# mini_controller_m328_2.net
KiCad netlist of a schematic drawn in EAGLE
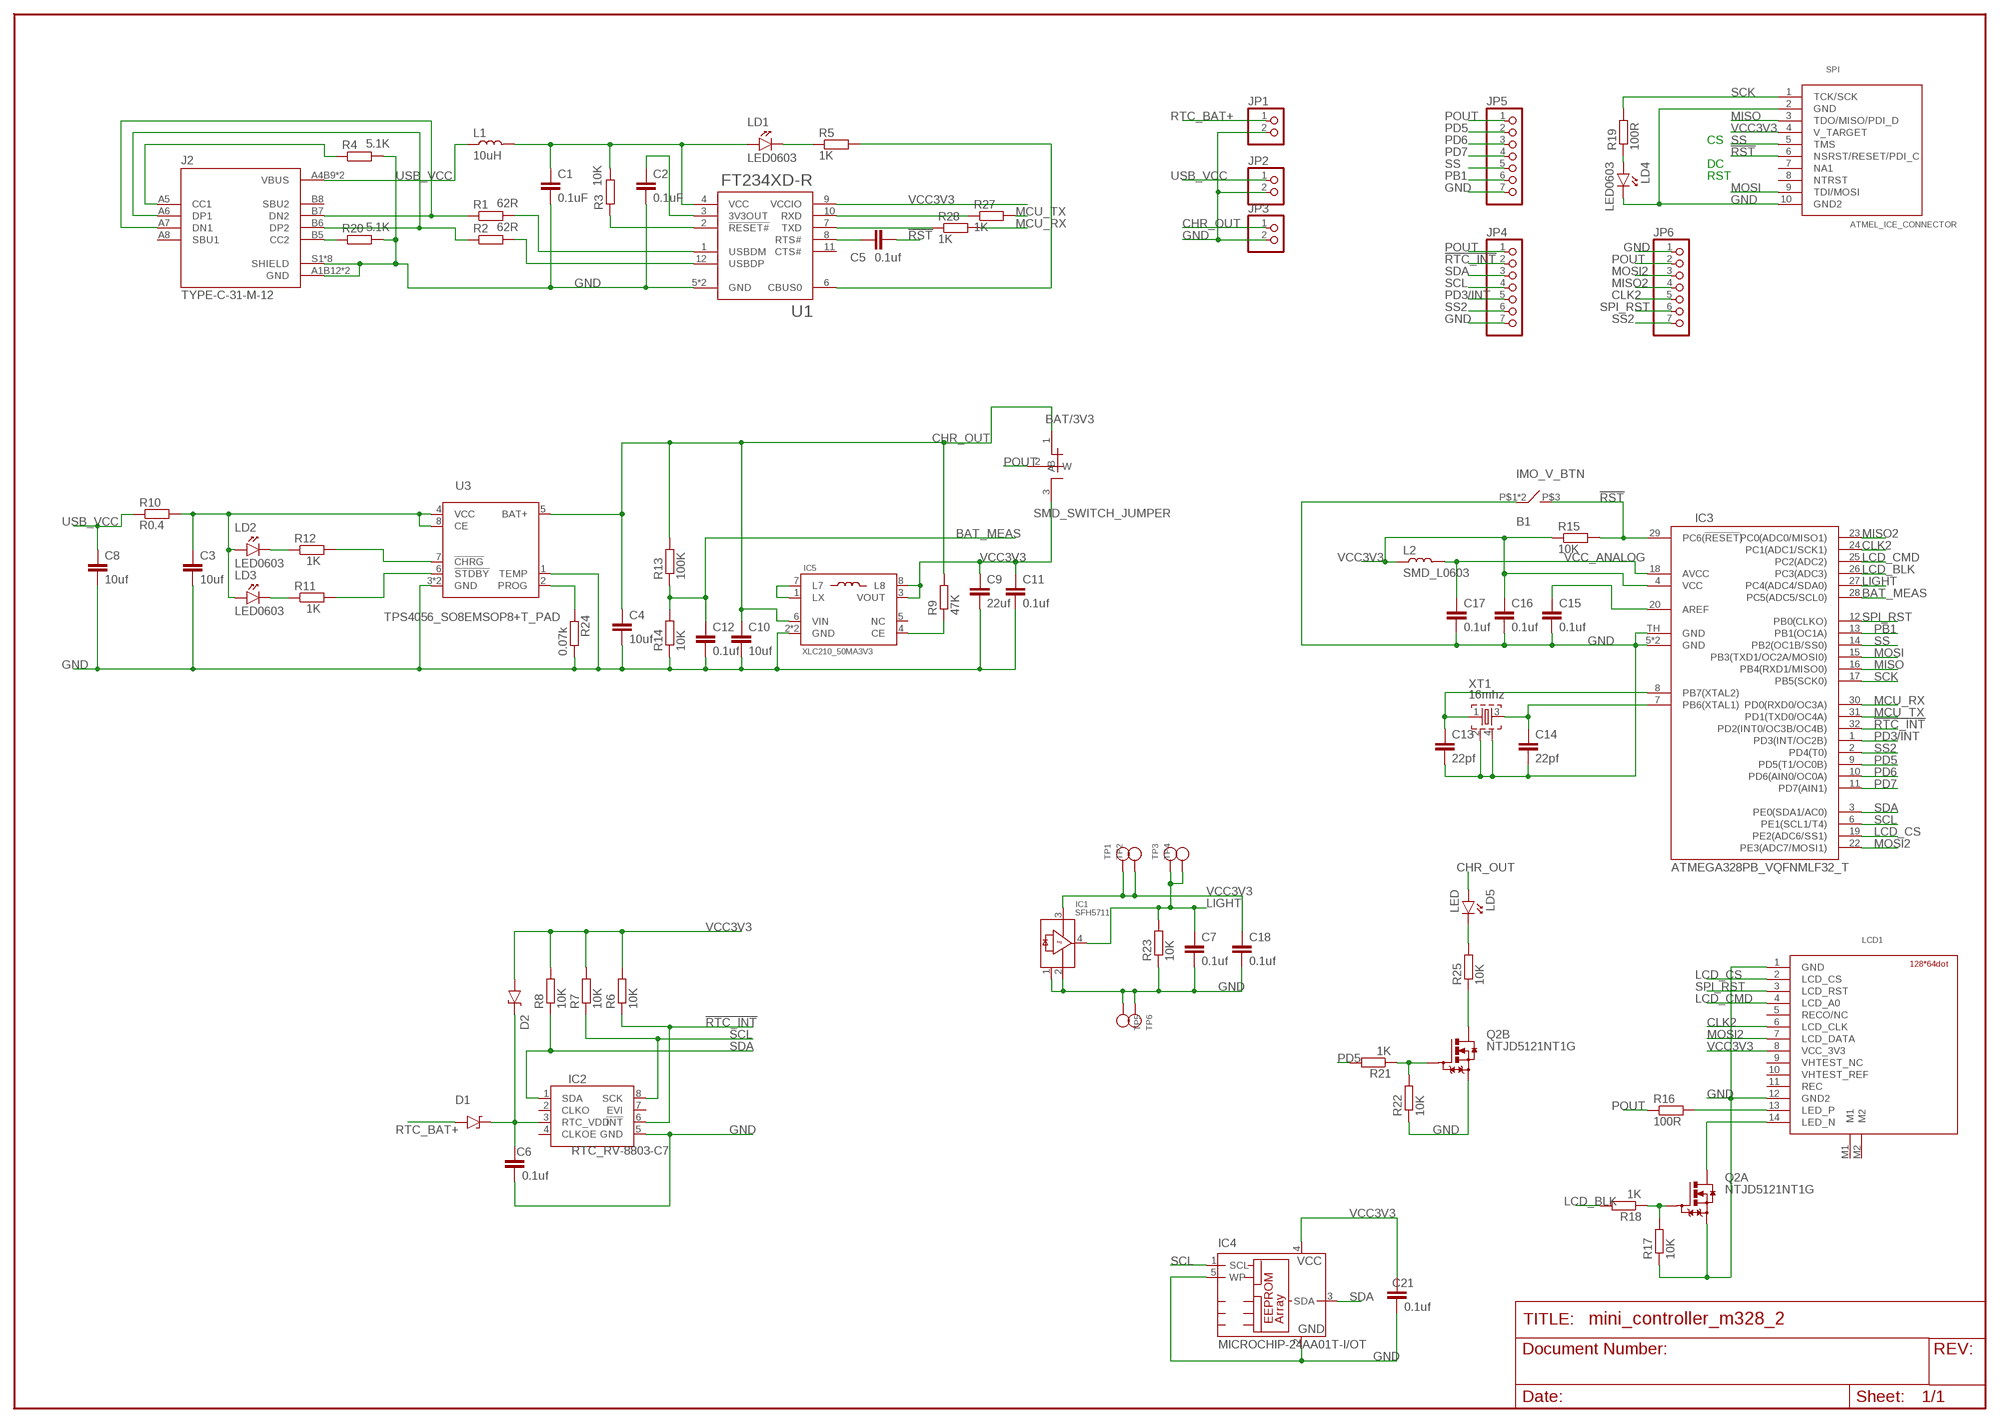
[diagram p0: schematic, sheet 1]

(export (version "E")
  (design (tool "Eeschema 10.0.6"))
  (components
    (comp (ref "B1")
      (value "IMO_V_BTN")
      (footprint "eagle-import:IMO_V_BNN")
      (libsource (lib "eagle-import") (part "IMO_V_BTN"))
    )
    (comp (ref "BAT/3V3")
      (value "SMD_SWITCH_JUMPER")
      (footprint "eagle-import:0603_JUMP")
      (libsource (lib "eagle-import") (part "SMD_SWITCH_JUMPER"))
    )
    (comp (ref "C1")
      (value "0.1uF")
      (footprint "eagle-import:0603")
      (libsource (lib "eagle-import") (part "SMD_C0603"))
    )
    (comp (ref "C2")
      (value "0.1uF")
      (footprint "eagle-import:0603")
      (libsource (lib "eagle-import") (part "SMD_C0603"))
    )
    (comp (ref "C3")
      (value "10uf")
      (footprint "eagle-import:1206")
      (libsource (lib "eagle-import") (part "SMD_C1206"))
    )
    (comp (ref "C4")
      (value "10uf")
      (footprint "eagle-import:1206")
      (libsource (lib "eagle-import") (part "SMD_C1206"))
    )
    (comp (ref "C5")
      (value "0.1uf")
      (footprint "eagle-import:0603")
      (libsource (lib "eagle-import") (part "SMD_C0603"))
    )
    (comp (ref "C6")
      (value "0.1uf")
      (footprint "eagle-import:0603")
      (libsource (lib "eagle-import") (part "SMD_C0603"))
    )
    (comp (ref "C7")
      (value "0.1uf")
      (footprint "eagle-import:0603")
      (libsource (lib "eagle-import") (part "SMD_C0603"))
    )
    (comp (ref "C8")
      (value "10uf")
      (footprint "eagle-import:1206")
      (libsource (lib "eagle-import") (part "SMD_C1206"))
    )
    (comp (ref "C9")
      (value "22uf")
      (footprint "eagle-import:0805")
      (libsource (lib "eagle-import") (part "SMD_C0805"))
    )
    (comp (ref "C10")
      (value "10uf")
      (footprint "eagle-import:0603")
      (libsource (lib "eagle-import") (part "SMD_C0603"))
    )
    (comp (ref "C11")
      (value "0.1uf")
      (footprint "eagle-import:0603")
      (libsource (lib "eagle-import") (part "SMD_C0603"))
    )
    (comp (ref "C12")
      (value "0.1uf")
      (footprint "eagle-import:0603")
      (libsource (lib "eagle-import") (part "SMD_C0603"))
    )
    (comp (ref "C13")
      (value "22pf")
      (footprint "eagle-import:0603")
      (libsource (lib "eagle-import") (part "SMD_C0603"))
    )
    (comp (ref "C14")
      (value "22pf")
      (footprint "eagle-import:0603")
      (libsource (lib "eagle-import") (part "SMD_C0603"))
    )
    (comp (ref "C15")
      (value "0.1uf")
      (footprint "eagle-import:0603")
      (libsource (lib "eagle-import") (part "SMD_C0603"))
    )
    (comp (ref "C16")
      (value "0.1uf")
      (footprint "eagle-import:0603")
      (libsource (lib "eagle-import") (part "SMD_C0603"))
    )
    (comp (ref "C17")
      (value "0.1uf")
      (footprint "eagle-import:0603")
      (libsource (lib "eagle-import") (part "SMD_C0603"))
    )
    (comp (ref "C18")
      (value "0.1uf")
      (footprint "eagle-import:0603")
      (libsource (lib "eagle-import") (part "SMD_C0603"))
    )
    (comp (ref "C21")
      (value "0.1uf")
      (footprint "eagle-import:0603")
      (libsource (lib "eagle-import") (part "SMD_C0603"))
    )
    (comp (ref "D1")
      (value "D_SOD323")
      (footprint "eagle-import:SOD-323_D")
      (libsource (lib "eagle-import") (part "D_SOD323"))
    )
    (comp (ref "D2")
      (value "D_SOD323")
      (footprint "eagle-import:SOD-323_D")
      (libsource (lib "eagle-import") (part "D_SOD323"))
    )
    (comp (ref "IC1")
      (value "SFH5711")
      (footprint "eagle-import:SFH5711")
      (fields (field (name "MF") "OSRAM Opto"))
      (libsource (lib "eagle-import") (part "SFH5711"))
    )
    (comp (ref "IC2")
      (value "RTC_RV-8803-C7")
      (footprint "eagle-import:C7_RTC")
      (libsource (lib "eagle-import") (part "RTC_RV-8803-C7"))
    )
    (comp (ref "IC3")
      (value "ATMEGA328PB_VQFNMLF32_T")
      (footprint "eagle-import:MLF32-TH")
      (libsource (lib "eagle-import") (part "ATMEGA328PB_VQFNMLF32_T"))
    )
    (comp (ref "IC4")
      (value "MICROCHIP-24AA01T-I/OT")
      (footprint "eagle-import:SOT-23(5)")
      (libsource (lib "eagle-import") (part "MICROCHIP-24AA01T-I/OT"))
    )
    (comp (ref "IC5")
      (value "XLC210_50MA3V3")
      (footprint "eagle-import:XCL210_50MA3V3")
      (libsource (lib "eagle-import") (part "XLC210_50MA3V3"))
    )
    (comp (ref "J2")
      (value "TYPE-C-31-M-12")
      (footprint "eagle-import:HRO_TYPE-C-31-M-12")
      (fields (field (name "MF") "HRO Electronics Co., Ltd."))
      (libsource (lib "eagle-import") (part "TYPE-C-31-M-12"))
    )
    (comp (ref "JP1")
      (value "PINHD-1X2")
      (footprint "eagle-import:1X02")
      (libsource (lib "eagle-import") (part "PINHD-1X2"))
    )
    (comp (ref "JP2")
      (value "PINHD-1X2")
      (footprint "eagle-import:1X02")
      (libsource (lib "eagle-import") (part "PINHD-1X2"))
    )
    (comp (ref "JP3")
      (value "PINHD-1X2")
      (footprint "eagle-import:1X02")
      (libsource (lib "eagle-import") (part "PINHD-1X2"))
    )
    (comp (ref "JP4")
      (value "PINHD-1X7")
      (footprint "eagle-import:1X07")
      (libsource (lib "eagle-import") (part "PINHD-1X7"))
    )
    (comp (ref "JP5")
      (value "PINHD-1X7")
      (footprint "eagle-import:1X07")
      (libsource (lib "eagle-import") (part "PINHD-1X7"))
    )
    (comp (ref "JP6")
      (value "PINHD-1X7")
      (footprint "eagle-import:1X07")
      (libsource (lib "eagle-import") (part "PINHD-1X7"))
    )
    (comp (ref "L1")
      (value "10uH")
      (footprint "eagle-import:0603")
      (libsource (lib "eagle-import") (part "SMD_L0603"))
    )
    (comp (ref "L2")
      (value "SMD_L0603")
      (footprint "eagle-import:0603")
      (libsource (lib "eagle-import") (part "SMD_L0603"))
    )
    (comp (ref "LCD1")
      (value "ALE_LCD_128X64")
      (footprint "eagle-import:ALE_LCD_14PIN_CONNECTOR")
      (libsource (lib "eagle-import") (part "ALE_LCD_128X64"))
    )
    (comp (ref "LD1")
      (value "LED0603")
      (footprint "eagle-import:0603_P")
      (libsource (lib "eagle-import") (part "LED0603"))
    )
    (comp (ref "LD2")
      (value "LED0603")
      (footprint "eagle-import:0603_P")
      (libsource (lib "eagle-import") (part "LED0603"))
    )
    (comp (ref "LD3")
      (value "LED0603")
      (footprint "eagle-import:0603_P")
      (libsource (lib "eagle-import") (part "LED0603"))
    )
    (comp (ref "LD4")
      (value "LED0603")
      (footprint "eagle-import:0603_P")
      (libsource (lib "eagle-import") (part "LED0603"))
    )
    (comp (ref "LD5")
      (value "LED")
      (footprint "eagle-import:3MM_DIP_LED")
      (libsource (lib "eagle-import") (part "LED"))
    )
    (comp (ref "Q2")
      (value "NTJD5121NT1G")
      (footprint "eagle-import:SOT363")
      (fields (field (name "MF") "ON SEMICONDUCTOR"))
      (libsource (lib "eagle-import") (part "NTJD5121NT1G"))
    )
    (comp (ref "R1")
      (value "62R")
      (footprint "eagle-import:0603")
      (libsource (lib "eagle-import") (part "SMD_R0603"))
    )
    (comp (ref "R2")
      (value "62R")
      (footprint "eagle-import:0603")
      (libsource (lib "eagle-import") (part "SMD_R0603"))
    )
    (comp (ref "R3")
      (value "10K")
      (footprint "eagle-import:0603")
      (libsource (lib "eagle-import") (part "SMD_R0603"))
    )
    (comp (ref "R4")
      (value "5.1K")
      (footprint "eagle-import:0603")
      (libsource (lib "eagle-import") (part "SMD_R0603"))
    )
    (comp (ref "R5")
      (value "1K")
      (footprint "eagle-import:0603")
      (libsource (lib "eagle-import") (part "SMD_R0603"))
    )
    (comp (ref "R6")
      (value "10K")
      (footprint "eagle-import:0603")
      (libsource (lib "eagle-import") (part "SMD_R0603"))
    )
    (comp (ref "R7")
      (value "10K")
      (footprint "eagle-import:0603")
      (libsource (lib "eagle-import") (part "SMD_R0603"))
    )
    (comp (ref "R8")
      (value "10K")
      (footprint "eagle-import:0603")
      (libsource (lib "eagle-import") (part "SMD_R0603"))
    )
    (comp (ref "R9")
      (value "47K")
      (footprint "eagle-import:0603")
      (libsource (lib "eagle-import") (part "SMD_R0603"))
    )
    (comp (ref "R10")
      (value "R0.4")
      (footprint "eagle-import:1206")
      (libsource (lib "eagle-import") (part "SMD_R1206"))
    )
    (comp (ref "R11")
      (value "1K")
      (footprint "eagle-import:0603")
      (libsource (lib "eagle-import") (part "SMD_R0603"))
    )
    (comp (ref "R12")
      (value "1K")
      (footprint "eagle-import:0603")
      (libsource (lib "eagle-import") (part "SMD_R0603"))
    )
    (comp (ref "R13")
      (value "100K")
      (footprint "eagle-import:0603")
      (libsource (lib "eagle-import") (part "SMD_R0603"))
    )
    (comp (ref "R14")
      (value "10K")
      (footprint "eagle-import:0603")
      (libsource (lib "eagle-import") (part "SMD_R0603"))
    )
    (comp (ref "R15")
      (value "10K")
      (footprint "eagle-import:0603")
      (libsource (lib "eagle-import") (part "SMD_R0603"))
    )
    (comp (ref "R16")
      (value "100R")
      (footprint "eagle-import:0603")
      (libsource (lib "eagle-import") (part "SMD_R0603"))
    )
    (comp (ref "R17")
      (value "10K")
      (footprint "eagle-import:0603")
      (libsource (lib "eagle-import") (part "SMD_R0603"))
    )
    (comp (ref "R18")
      (value "1K")
      (footprint "eagle-import:0603")
      (libsource (lib "eagle-import") (part "SMD_R0603"))
    )
    (comp (ref "R19")
      (value "100R")
      (footprint "eagle-import:0603")
      (libsource (lib "eagle-import") (part "SMD_R0603"))
    )
    (comp (ref "R20")
      (value "5.1K")
      (footprint "eagle-import:0603")
      (libsource (lib "eagle-import") (part "SMD_R0603"))
    )
    (comp (ref "R21")
      (value "1K")
      (footprint "eagle-import:0603")
      (libsource (lib "eagle-import") (part "SMD_R0603"))
    )
    (comp (ref "R22")
      (value "10K")
      (footprint "eagle-import:0603")
      (libsource (lib "eagle-import") (part "SMD_R0603"))
    )
    (comp (ref "R23")
      (value "10K")
      (footprint "eagle-import:0603")
      (libsource (lib "eagle-import") (part "SMD_R0603"))
    )
    (comp (ref "R24")
      (value "0.07k")
      (footprint "eagle-import:0603")
      (libsource (lib "eagle-import") (part "SMD_R0603"))
    )
    (comp (ref "R25")
      (value "10K")
      (footprint "eagle-import:0603")
      (libsource (lib "eagle-import") (part "SMD_R0603"))
    )
    (comp (ref "R27")
      (value "1K")
      (footprint "eagle-import:0603")
      (libsource (lib "eagle-import") (part "SMD_R0603"))
    )
    (comp (ref "R28")
      (value "1K")
      (footprint "eagle-import:0603")
      (libsource (lib "eagle-import") (part "SMD_R0603"))
    )
    (comp (ref "SPI")
      (value "ATMEL_ICE_CONNECTOR")
      (footprint "eagle-import:MINI10P_SPI_JTAG_PDI")
      (libsource (lib "eagle-import") (part "ATMEL_ICE_CONNECTOR"))
    )
    (comp (ref "TP1")
      (value "TEST_POINT_D2MM")
      (footprint "eagle-import:TP")
      (libsource (lib "eagle-import") (part "TEST_POINT_D2MM"))
    )
    (comp (ref "TP2")
      (value "TEST_POINT_D2MM")
      (footprint "eagle-import:TP")
      (libsource (lib "eagle-import") (part "TEST_POINT_D2MM"))
    )
    (comp (ref "TP3")
      (value "TEST_POINT_D2MM")
      (footprint "eagle-import:TP")
      (libsource (lib "eagle-import") (part "TEST_POINT_D2MM"))
    )
    (comp (ref "TP4")
      (value "TEST_POINT_D2MM")
      (footprint "eagle-import:TP")
      (libsource (lib "eagle-import") (part "TEST_POINT_D2MM"))
    )
    (comp (ref "TP5")
      (value "TEST_POINT_D2MM")
      (footprint "eagle-import:TP")
      (libsource (lib "eagle-import") (part "TEST_POINT_D2MM"))
    )
    (comp (ref "TP6")
      (value "TEST_POINT_D2MM")
      (footprint "eagle-import:TP")
      (libsource (lib "eagle-import") (part "TEST_POINT_D2MM"))
    )
    (comp (ref "U1")
      (value "FT234XD-R")
      (footprint "eagle-import:IC_FT234XD-R")
      (fields (field (name "MF") "FTDI,"))
      (libsource (lib "eagle-import") (part "FT234XD-R"))
    )
    (comp (ref "U3")
      (value "TPS4056_SO8EMSOP8+T_PAD")
      (footprint "eagle-import:EMSOP8+TPAD")
      (libsource (lib "eagle-import") (part "TPS4056_SO8EMSOP8+T_PAD"))
    )
    (comp (ref "XT1")
      (value "16mhz")
      (footprint "eagle-import:QUARTZ_3X3MM")
      (libsource (lib "eagle-import") (part "QUARTZ_ZQ"))
    )
  )
  (nets
    (net (code "1") (name "/BAT_MEAS") (class "Default")
      (node (ref "C12") (pin "1") (pinfunction "1_1") (pintype "passive"))
      (node (ref "IC3") (pin "28") (pinfunction "PC5(ADC5/SCL0)_28") (pintype "bidirectional"))
      (node (ref "R13") (pin "1") (pinfunction "1_1") (pintype "passive"))
      (node (ref "R14") (pin "2") (pinfunction "2_2") (pintype "passive"))
    )
    (net (code "2") (name "/CHR_OUT") (class "Default")
      (node (ref "BAT/3V3") (pin "1") (pinfunction "A_1") (pintype "bidirectional"))
      (node (ref "C10") (pin "1") (pinfunction "1_1") (pintype "passive"))
      (node (ref "C4") (pin "1") (pinfunction "1_1") (pintype "passive"))
      (node (ref "IC5") (pin "6") (pinfunction "VIN_6") (pintype "bidirectional"))
      (node (ref "JP3") (pin "1") (pinfunction "1_1") (pintype "passive"))
      (node (ref "LD5") (pin "A") (pinfunction "A_A") (pintype "bidirectional"))
      (node (ref "R13") (pin "2") (pinfunction "2_2") (pintype "passive"))
      (node (ref "R9") (pin "2") (pinfunction "2_2") (pintype "passive"))
      (node (ref "U3") (pin "5") (pinfunction "BAT+_5") (pintype "bidirectional"))
    )
    (net (code "3") (name "/CLK2") (class "Default")
      (node (ref "IC3") (pin "24") (pinfunction "PC1(ADC1/SCK1)_24") (pintype "bidirectional"))
      (node (ref "JP6") (pin "5") (pinfunction "5_5") (pintype "passive"))
      (node (ref "LCD1") (pin "6") (pinfunction "LCD_CLK_6") (pintype "bidirectional"))
    )
    (net (code "4") (name "/GND") (class "Default")
      (node (ref "B1") (pin "P$1") (pinfunction "1_P$1") (pintype "bidirectional"))
      (node (ref "B1") (pin "P$2") (pinfunction "1_P$2") (pintype "bidirectional"))
      (node (ref "C1") (pin "2") (pinfunction "2_2") (pintype "passive"))
      (node (ref "C10") (pin "2") (pinfunction "2_2") (pintype "passive"))
      (node (ref "C11") (pin "2") (pinfunction "2_2") (pintype "passive"))
      (node (ref "C12") (pin "2") (pinfunction "2_2") (pintype "passive"))
      (node (ref "C13") (pin "2") (pinfunction "2_2") (pintype "passive"))
      (node (ref "C14") (pin "2") (pinfunction "2_2") (pintype "passive"))
      (node (ref "C15") (pin "2") (pinfunction "2_2") (pintype "passive"))
      (node (ref "C16") (pin "2") (pinfunction "2_2") (pintype "passive"))
      (node (ref "C17") (pin "2") (pinfunction "2_2") (pintype "passive"))
      (node (ref "C18") (pin "2") (pinfunction "2_2") (pintype "passive"))
      (node (ref "C2") (pin "2") (pinfunction "2_2") (pintype "passive"))
      (node (ref "C21") (pin "2") (pinfunction "2_2") (pintype "passive"))
      (node (ref "C3") (pin "2") (pinfunction "2_2") (pintype "passive"))
      (node (ref "C4") (pin "2") (pinfunction "2_2") (pintype "passive"))
      (node (ref "C6") (pin "2") (pinfunction "2_2") (pintype "passive"))
      (node (ref "C7") (pin "2") (pinfunction "2_2") (pintype "passive"))
      (node (ref "C8") (pin "2") (pinfunction "2_2") (pintype "passive"))
      (node (ref "C9") (pin "2") (pinfunction "2_2") (pintype "passive"))
      (node (ref "IC1") (pin "1") (pinfunction "1_1") (pintype "bidirectional"))
      (node (ref "IC1") (pin "2") (pinfunction "2_2") (pintype "bidirectional"))
      (node (ref "IC2") (pin "5") (pinfunction "GND_5") (pintype "bidirectional"))
      (node (ref "IC3") (pin "21") (pinfunction "GND_21") (pintype "power_in"))
      (node (ref "IC3") (pin "5") (pinfunction "GND_5") (pintype "power_in"))
      (node (ref "IC3") (pin "TH") (pinfunction "GND_TH") (pintype "power_in"))
      (node (ref "IC4") (pin "2") (pinfunction "GND_2") (pintype "power_in"))
      (node (ref "IC4") (pin "5") (pinfunction "WP_5") (pintype "input"))
      (node (ref "IC5") (pin "2") (pinfunction "GND_2") (pintype "bidirectional"))
      (node (ref "IC5") (pin "9") (pinfunction "GND_9") (pintype "bidirectional"))
      (node (ref "J2") (pin "A1B12") (pinfunction "GND_A1B12") (pintype "power_in"))
      (node (ref "J2") (pin "B1A12") (pinfunction "GND_B1A12") (pintype "power_in"))
      (node (ref "J2") (pin "S1") (pinfunction "SHIELD_S1") (pintype "passive"))
      (node (ref "J2") (pin "S2") (pinfunction "SHIELD_S2") (pintype "passive"))
      (node (ref "J2") (pin "S3") (pinfunction "SHIELD_S3") (pintype "passive"))
      (node (ref "J2") (pin "S4") (pinfunction "SHIELD_S4") (pintype "passive"))
      (node (ref "J2") (pin "S5") (pinfunction "SHIELD_S5") (pintype "passive"))
      (node (ref "J2") (pin "S6") (pinfunction "SHIELD_S6") (pintype "passive"))
      (node (ref "J2") (pin "S7") (pinfunction "SHIELD_S7") (pintype "passive"))
      (node (ref "J2") (pin "S8") (pinfunction "SHIELD_S8") (pintype "passive"))
      (node (ref "JP1") (pin "2") (pinfunction "2_2") (pintype "passive"))
      (node (ref "JP2") (pin "2") (pinfunction "2_2") (pintype "passive"))
      (node (ref "JP3") (pin "2") (pinfunction "2_2") (pintype "passive"))
      (node (ref "JP4") (pin "7") (pinfunction "7_7") (pintype "passive"))
      (node (ref "JP5") (pin "7") (pinfunction "7_7") (pintype "passive"))
      (node (ref "JP6") (pin "1") (pinfunction "1_1") (pintype "passive"))
      (node (ref "LCD1") (pin "1") (pinfunction "GND_1") (pintype "bidirectional"))
      (node (ref "LCD1") (pin "12") (pinfunction "GND2_12") (pintype "bidirectional"))
      (node (ref "LD4") (pin "1") (pinfunction "K_1") (pintype "bidirectional"))
      (node (ref "Q2") (pin "1") (pinfunction "S_1") (pintype "passive"))
      (node (ref "Q2") (pin "4") (pinfunction "S_4") (pintype "passive"))
      (node (ref "R14") (pin "1") (pinfunction "1_1") (pintype "passive"))
      (node (ref "R17") (pin "1") (pinfunction "1_1") (pintype "passive"))
      (node (ref "R20") (pin "2") (pinfunction "2_2") (pintype "passive"))
      (node (ref "R22") (pin "1") (pinfunction "1_1") (pintype "passive"))
      (node (ref "R23") (pin "1") (pinfunction "1_1") (pintype "passive"))
      (node (ref "R24") (pin "2") (pinfunction "2_2") (pintype "passive"))
      (node (ref "R4") (pin "2") (pinfunction "2_2") (pintype "passive"))
      (node (ref "SPI") (pin "10") (pinfunction "GND2_10") (pintype "bidirectional"))
      (node (ref "SPI") (pin "2") (pinfunction "GND_2") (pintype "bidirectional"))
      (node (ref "TP5") (pin "P$1") (pinfunction "1_P$1") (pintype "bidirectional"))
      (node (ref "TP6") (pin "P$1") (pinfunction "1_P$1") (pintype "bidirectional"))
      (node (ref "U1") (pin "13") (pinfunction "GND_13") (pintype "power_in"))
      (node (ref "U1") (pin "5") (pinfunction "GND_5") (pintype "power_in"))
      (node (ref "U3") (pin "1") (pinfunction "TEMP_1") (pintype "bidirectional"))
      (node (ref "U3") (pin "3") (pinfunction "GND_3") (pintype "bidirectional"))
      (node (ref "U3") (pin "TPAD") (pinfunction "GND_TPAD") (pintype "bidirectional"))
      (node (ref "XT1") (pin "2") (pinfunction "2_2") (pintype "passive"))
      (node (ref "XT1") (pin "4") (pinfunction "4_4") (pintype "passive"))
    )
    (net (code "5") (name "/LCD_BLK") (class "Default")
      (node (ref "IC3") (pin "26") (pinfunction "PC3(ADC3)_26") (pintype "bidirectional"))
      (node (ref "R18") (pin "2") (pinfunction "2_2") (pintype "passive"))
    )
    (net (code "6") (name "/LCD_CMD") (class "Default")
      (node (ref "IC3") (pin "25") (pinfunction "PC2(ADC2)_25") (pintype "bidirectional"))
      (node (ref "LCD1") (pin "4") (pinfunction "LCD_A0_4") (pintype "bidirectional"))
    )
    (net (code "7") (name "/LCD_CS") (class "Default")
      (node (ref "IC3") (pin "19") (pinfunction "PE2(ADC6/SS1)_19") (pintype "bidirectional"))
      (node (ref "LCD1") (pin "2") (pinfunction "LCD_CS_2") (pintype "bidirectional"))
    )
    (net (code "8") (name "/LIGHT") (class "Default")
      (node (ref "C7") (pin "1") (pinfunction "1_1") (pintype "passive"))
      (node (ref "IC1") (pin "4") (pinfunction "4_4") (pintype "bidirectional"))
      (node (ref "IC3") (pin "27") (pinfunction "PC4(ADC4/SDA0)_27") (pintype "bidirectional"))
      (node (ref "R23") (pin "2") (pinfunction "2_2") (pintype "passive"))
      (node (ref "TP3") (pin "P$1") (pinfunction "1_P$1") (pintype "bidirectional"))
      (node (ref "TP4") (pin "P$1") (pinfunction "1_P$1") (pintype "bidirectional"))
    )
    (net (code "9") (name "/MCU_RX") (class "Default")
      (node (ref "IC3") (pin "30") (pinfunction "PD0(RXD0/OC3A)_30") (pintype "bidirectional"))
      (node (ref "R28") (pin "2") (pinfunction "2_2") (pintype "passive"))
    )
    (net (code "10") (name "/MCU_TX") (class "Default")
      (node (ref "IC3") (pin "31") (pinfunction "PD1(TXD0/OC4A)_31") (pintype "bidirectional"))
      (node (ref "R27") (pin "2") (pinfunction "2_2") (pintype "passive"))
    )
    (net (code "11") (name "/MISO") (class "Default")
      (node (ref "IC3") (pin "16") (pinfunction "PB4(RXD1/MISO0)_16") (pintype "bidirectional"))
      (node (ref "SPI") (pin "3") (pinfunction "TDO/MISO/PDI_D_3") (pintype "bidirectional"))
    )
    (net (code "12") (name "/MISO2") (class "Default")
      (node (ref "IC3") (pin "23") (pinfunction "PC0(ADC0/MISO1)_23") (pintype "bidirectional"))
      (node (ref "JP6") (pin "4") (pinfunction "4_4") (pintype "passive"))
    )
    (net (code "13") (name "/MOSI") (class "Default")
      (node (ref "IC3") (pin "15") (pinfunction "PB3(TXD1/OC2A/MOSI0)_15") (pintype "bidirectional"))
      (node (ref "SPI") (pin "9") (pinfunction "TDI/MOSI_9") (pintype "bidirectional"))
    )
    (net (code "14") (name "/MOSI2") (class "Default")
      (node (ref "IC3") (pin "22") (pinfunction "PE3(ADC7/MOSI1)_22") (pintype "bidirectional"))
      (node (ref "JP6") (pin "3") (pinfunction "3_3") (pintype "passive"))
      (node (ref "LCD1") (pin "7") (pinfunction "LCD_DATA_7") (pintype "bidirectional"))
    )
    (net (code "15") (name "/PB1") (class "Default")
      (node (ref "IC3") (pin "13") (pinfunction "PB1(OC1A)_13") (pintype "bidirectional"))
      (node (ref "JP5") (pin "6") (pinfunction "6_6") (pintype "passive"))
    )
    (net (code "16") (name "/PD3{slash}INT") (class "Default")
      (node (ref "IC3") (pin "1") (pinfunction "PD3(INT/OC2B)_1") (pintype "bidirectional"))
      (node (ref "JP4") (pin "5") (pinfunction "5_5") (pintype "passive"))
    )
    (net (code "17") (name "/PD5") (class "Default")
      (node (ref "IC3") (pin "9") (pinfunction "PD5(T1/OC0B)_9") (pintype "bidirectional"))
      (node (ref "JP5") (pin "2") (pinfunction "2_2") (pintype "passive"))
      (node (ref "R21") (pin "2") (pinfunction "2_2") (pintype "passive"))
    )
    (net (code "18") (name "/PD6") (class "Default")
      (node (ref "IC3") (pin "10") (pinfunction "PD6(AIN0/OC0A)_10") (pintype "bidirectional"))
      (node (ref "JP5") (pin "3") (pinfunction "3_3") (pintype "passive"))
    )
    (net (code "19") (name "/PD7") (class "Default")
      (node (ref "IC3") (pin "11") (pinfunction "PD7(AIN1)_11") (pintype "bidirectional"))
      (node (ref "JP5") (pin "4") (pinfunction "4_4") (pintype "passive"))
    )
    (net (code "20") (name "/POUT") (class "Default")
      (node (ref "BAT/3V3") (pin "2") (pinfunction "W_2") (pintype "bidirectional"))
      (node (ref "JP4") (pin "1") (pinfunction "1_1") (pintype "passive"))
      (node (ref "JP5") (pin "1") (pinfunction "1_1") (pintype "passive"))
      (node (ref "JP6") (pin "2") (pinfunction "2_2") (pintype "passive"))
      (node (ref "R16") (pin "1") (pinfunction "1_1") (pintype "passive"))
    )
    (net (code "21") (name "/RTC_BAT+") (class "Default")
      (node (ref "D1") (pin "A") (pinfunction "A_A") (pintype "bidirectional"))
      (node (ref "JP1") (pin "1") (pinfunction "1_1") (pintype "passive"))
    )
    (net (code "22") (name "/SCK") (class "Default")
      (node (ref "IC3") (pin "17") (pinfunction "PB5(SCK0)_17") (pintype "bidirectional"))
      (node (ref "R19") (pin "2") (pinfunction "2_2") (pintype "passive"))
      (node (ref "SPI") (pin "1") (pinfunction "TCK/SCK_1") (pintype "bidirectional"))
    )
    (net (code "23") (name "/SCL") (class "Default")
      (node (ref "IC2") (pin "8") (pinfunction "SCK_8") (pintype "bidirectional"))
      (node (ref "IC3") (pin "6") (pinfunction "PE1(SCL1/T4)_6") (pintype "bidirectional"))
      (node (ref "IC4") (pin "1") (pinfunction "SCL_1") (pintype "input"))
      (node (ref "JP4") (pin "4") (pinfunction "4_4") (pintype "passive"))
      (node (ref "R7") (pin "1") (pinfunction "1_1") (pintype "passive"))
    )
    (net (code "24") (name "/SDA") (class "Default")
      (node (ref "IC2") (pin "1") (pinfunction "SDA_1") (pintype "bidirectional"))
      (node (ref "IC3") (pin "3") (pinfunction "PE0(SDA1/AC0)_3") (pintype "bidirectional"))
      (node (ref "IC4") (pin "3") (pinfunction "SDA_3") (pintype "bidirectional"))
      (node (ref "JP4") (pin "3") (pinfunction "3_3") (pintype "passive"))
      (node (ref "R8") (pin "1") (pinfunction "1_1") (pintype "passive"))
    )
    (net (code "25") (name "/SPI_RST") (class "Default")
      (node (ref "IC3") (pin "12") (pinfunction "PB0(CLKO)_12") (pintype "bidirectional"))
      (node (ref "JP6") (pin "6") (pinfunction "6_6") (pintype "passive"))
      (node (ref "LCD1") (pin "3") (pinfunction "LCD_RST_3") (pintype "bidirectional"))
    )
    (net (code "26") (name "/SS") (class "Default")
      (node (ref "IC3") (pin "14") (pinfunction "PB2(OC1B/SS0)_14") (pintype "bidirectional"))
      (node (ref "JP5") (pin "5") (pinfunction "5_5") (pintype "passive"))
      (node (ref "SPI") (pin "5") (pinfunction "TMS_5") (pintype "bidirectional"))
    )
    (net (code "27") (name "/SS2") (class "Default")
      (node (ref "IC3") (pin "2") (pinfunction "PD4(T0)_2") (pintype "bidirectional"))
      (node (ref "JP4") (pin "6") (pinfunction "6_6") (pintype "passive"))
      (node (ref "JP6") (pin "7") (pinfunction "7_7") (pintype "passive"))
    )
    (net (code "28") (name "/USB_VCC") (class "Default")
      (node (ref "C8") (pin "1") (pinfunction "1_1") (pintype "passive"))
      (node (ref "J2") (pin "A4B9") (pinfunction "VBUS_A4B9") (pintype "power_in"))
      (node (ref "J2") (pin "B4A9") (pinfunction "VBUS_B4A9") (pintype "power_in"))
      (node (ref "JP2") (pin "1") (pinfunction "1_1") (pintype "passive"))
      (node (ref "L1") (pin "1") (pinfunction "1_1") (pintype "passive"))
      (node (ref "R10") (pin "1") (pinfunction "1_1") (pintype "passive"))
    )
    (net (code "29") (name "/VCC3V3") (class "Default")
      (node (ref "BAT/3V3") (pin "3") (pinfunction "B_3") (pintype "bidirectional"))
      (node (ref "C11") (pin "1") (pinfunction "1_1") (pintype "passive"))
      (node (ref "C16") (pin "1") (pinfunction "1_1") (pintype "passive"))
      (node (ref "C18") (pin "1") (pinfunction "1_1") (pintype "passive"))
      (node (ref "C21") (pin "1") (pinfunction "1_1") (pintype "passive"))
      (node (ref "C9") (pin "1") (pinfunction "1_1") (pintype "passive"))
      (node (ref "D2") (pin "A") (pinfunction "A_A") (pintype "bidirectional"))
      (node (ref "IC1") (pin "3") (pinfunction "3_3") (pintype "bidirectional"))
      (node (ref "IC3") (pin "4") (pinfunction "VCC_4") (pintype "power_in"))
      (node (ref "IC4") (pin "4") (pinfunction "VCC_4") (pintype "power_in"))
      (node (ref "IC5") (pin "3") (pinfunction "VOUT_3") (pintype "bidirectional"))
      (node (ref "IC5") (pin "8") (pinfunction "L8_8") (pintype "bidirectional"))
      (node (ref "L2") (pin "1") (pinfunction "1_1") (pintype "passive"))
      (node (ref "LCD1") (pin "8") (pinfunction "VCC_3V3_8") (pintype "bidirectional"))
      (node (ref "R15") (pin "1") (pinfunction "1_1") (pintype "passive"))
      (node (ref "R6") (pin "2") (pinfunction "2_2") (pintype "passive"))
      (node (ref "R7") (pin "2") (pinfunction "2_2") (pintype "passive"))
      (node (ref "R8") (pin "2") (pinfunction "2_2") (pintype "passive"))
      (node (ref "SPI") (pin "4") (pinfunction "V_TARGET_4") (pintype "bidirectional"))
      (node (ref "TP1") (pin "P$1") (pinfunction "1_P$1") (pintype "bidirectional"))
      (node (ref "TP2") (pin "P$1") (pinfunction "1_P$1") (pintype "bidirectional"))
      (node (ref "U1") (pin "9") (pinfunction "VCCIO_9") (pintype "power_in"))
    )
    (net (code "30") (name "/VCC_ANALOG") (class "Default")
      (node (ref "C17") (pin "1") (pinfunction "1_1") (pintype "passive"))
      (node (ref "IC3") (pin "18") (pinfunction "AVCC_18") (pintype "power_in"))
      (node (ref "L2") (pin "2") (pinfunction "2_2") (pintype "passive"))
    )
    (net (code "31") (name "/~{RST}") (class "Default")
      (node (ref "B1") (pin "P$3") (pinfunction "4_P$3") (pintype "bidirectional"))
      (node (ref "C5") (pin "2") (pinfunction "2_2") (pintype "passive"))
      (node (ref "IC3") (pin "29") (pinfunction "PC6(~{RESET})_29") (pintype "bidirectional"))
      (node (ref "R15") (pin "2") (pinfunction "2_2") (pintype "passive"))
      (node (ref "SPI") (pin "6") (pinfunction "NSRST/RESET/PDI_C_6") (pintype "bidirectional"))
    )
    (net (code "32") (name "/~{RTC_INT}") (class "Default")
      (node (ref "IC2") (pin "6") (pinfunction "~{INT}_6") (pintype "bidirectional"))
      (node (ref "IC3") (pin "32") (pinfunction "PD2(INT0/OC3B/OC4B)_32") (pintype "bidirectional"))
      (node (ref "JP4") (pin "2") (pinfunction "2_2") (pintype "passive"))
      (node (ref "R6") (pin "1") (pinfunction "1_1") (pintype "passive"))
    )
    (net (code "33") (name "Net-(IC2-RTC_VDD)") (class "Default")
      (node (ref "C6") (pin "1") (pinfunction "1_1") (pintype "passive"))
      (node (ref "D1") (pin "K") (pinfunction "K_K") (pintype "bidirectional"))
      (node (ref "D2") (pin "K") (pinfunction "K_K") (pintype "bidirectional"))
      (node (ref "IC2") (pin "3") (pinfunction "RTC_VDD_3") (pintype "bidirectional"))
    )
    (net (code "34") (name "Net-(IC3-AREF)") (class "Default")
      (node (ref "C15") (pin "1") (pinfunction "1_1") (pintype "passive"))
      (node (ref "IC3") (pin "20") (pinfunction "AREF_20") (pintype "passive"))
    )
    (net (code "35") (name "Net-(IC3-PB6(XTAL1))") (class "Default")
      (node (ref "C14") (pin "1") (pinfunction "1_1") (pintype "passive"))
      (node (ref "IC3") (pin "7") (pinfunction "PB6(XTAL1)_7") (pintype "bidirectional"))
      (node (ref "XT1") (pin "3") (pinfunction "3_3") (pintype "passive"))
    )
    (net (code "36") (name "Net-(IC3-PB7(XTAL2))") (class "Default")
      (node (ref "C13") (pin "1") (pinfunction "1_1") (pintype "passive"))
      (node (ref "IC3") (pin "8") (pinfunction "PB7(XTAL2)_8") (pintype "bidirectional"))
      (node (ref "XT1") (pin "1") (pinfunction "1_1") (pintype "passive"))
    )
    (net (code "37") (name "Net-(IC5-CE)") (class "Default")
      (node (ref "IC5") (pin "4") (pinfunction "CE_4") (pintype "bidirectional"))
      (node (ref "R9") (pin "1") (pinfunction "1_1") (pintype "passive"))
    )
    (net (code "38") (name "Net-(IC5-L7)") (class "Default")
      (node (ref "IC5") (pin "1") (pinfunction "LX_1") (pintype "bidirectional"))
      (node (ref "IC5") (pin "7") (pinfunction "L7_7") (pintype "bidirectional"))
    )
    (net (code "39") (name "Net-(J2-CC1)") (class "Default")
      (node (ref "J2") (pin "A5") (pinfunction "CC1_A5") (pintype "bidirectional"))
      (node (ref "R4") (pin "1") (pinfunction "1_1") (pintype "passive"))
    )
    (net (code "40") (name "Net-(J2-CC2)") (class "Default")
      (node (ref "J2") (pin "B5") (pinfunction "CC2_B5") (pintype "bidirectional"))
      (node (ref "R20") (pin "1") (pinfunction "1_1") (pintype "passive"))
    )
    (net (code "41") (name "Net-(J2-DN1)") (class "Default")
      (node (ref "J2") (pin "A7") (pinfunction "DN1_A7") (pintype "bidirectional"))
      (node (ref "J2") (pin "B7") (pinfunction "DN2_B7") (pintype "bidirectional"))
      (node (ref "R1") (pin "1") (pinfunction "1_1") (pintype "passive"))
    )
    (net (code "42") (name "Net-(J2-DP1)") (class "Default")
      (node (ref "J2") (pin "A6") (pinfunction "DP1_A6") (pintype "bidirectional"))
      (node (ref "J2") (pin "B6") (pinfunction "DP2_B6") (pintype "bidirectional"))
      (node (ref "R2") (pin "1") (pinfunction "1_1") (pintype "passive"))
    )
    (net (code "43") (name "Net-(LCD1-LED_N)") (class "Default")
      (node (ref "LCD1") (pin "14") (pinfunction "LED_N_14") (pintype "bidirectional"))
      (node (ref "Q2") (pin "6") (pinfunction "D_6") (pintype "passive"))
    )
    (net (code "44") (name "Net-(LCD1-LED_P)") (class "Default")
      (node (ref "LCD1") (pin "13") (pinfunction "LED_P_13") (pintype "bidirectional"))
      (node (ref "R16") (pin "2") (pinfunction "2_2") (pintype "passive"))
    )
    (net (code "45") (name "Net-(LD1-A)") (class "Default")
      (node (ref "C1") (pin "1") (pinfunction "1_1") (pintype "passive"))
      (node (ref "L1") (pin "2") (pinfunction "2_2") (pintype "passive"))
      (node (ref "LD1") (pin "2") (pinfunction "A_2") (pintype "bidirectional"))
      (node (ref "R3") (pin "2") (pinfunction "2_2") (pintype "passive"))
      (node (ref "U1") (pin "4") (pinfunction "VCC_4") (pintype "power_in"))
    )
    (net (code "46") (name "Net-(LD1-K)") (class "Default")
      (node (ref "LD1") (pin "1") (pinfunction "K_1") (pintype "bidirectional"))
      (node (ref "R5") (pin "1") (pinfunction "1_1") (pintype "passive"))
    )
    (net (code "47") (name "Net-(LD2-A)") (class "Default")
      (node (ref "C3") (pin "1") (pinfunction "1_1") (pintype "passive"))
      (node (ref "LD2") (pin "2") (pinfunction "A_2") (pintype "bidirectional"))
      (node (ref "LD3") (pin "2") (pinfunction "A_2") (pintype "bidirectional"))
      (node (ref "R10") (pin "2") (pinfunction "2_2") (pintype "passive"))
      (node (ref "U3") (pin "4") (pinfunction "VCC_4") (pintype "bidirectional"))
      (node (ref "U3") (pin "8") (pinfunction "CE_8") (pintype "bidirectional"))
    )
    (net (code "48") (name "Net-(LD2-K)") (class "Default")
      (node (ref "LD2") (pin "1") (pinfunction "K_1") (pintype "bidirectional"))
      (node (ref "R12") (pin "1") (pinfunction "1_1") (pintype "passive"))
    )
    (net (code "49") (name "Net-(LD3-K)") (class "Default")
      (node (ref "LD3") (pin "1") (pinfunction "K_1") (pintype "bidirectional"))
      (node (ref "R11") (pin "1") (pinfunction "1_1") (pintype "passive"))
    )
    (net (code "50") (name "Net-(LD4-A)") (class "Default")
      (node (ref "LD4") (pin "2") (pinfunction "A_2") (pintype "bidirectional"))
      (node (ref "R19") (pin "1") (pinfunction "1_1") (pintype "passive"))
    )
    (net (code "51") (name "Net-(LD5-PadK)") (class "Default")
      (node (ref "LD5") (pin "K") (pinfunction "K_K") (pintype "bidirectional"))
      (node (ref "R25") (pin "2") (pinfunction "2_2") (pintype "passive"))
    )
    (net (code "52") (name "Net-(Q2A-G)") (class "Default")
      (node (ref "Q2") (pin "2") (pinfunction "G_2") (pintype "passive"))
      (node (ref "R17") (pin "2") (pinfunction "2_2") (pintype "passive"))
      (node (ref "R18") (pin "1") (pinfunction "1_1") (pintype "passive"))
    )
    (net (code "53") (name "Net-(Q2B-D)") (class "Default")
      (node (ref "Q2") (pin "3") (pinfunction "D_3") (pintype "passive"))
      (node (ref "R25") (pin "1") (pinfunction "1_1") (pintype "passive"))
    )
    (net (code "54") (name "Net-(Q2B-G)") (class "Default")
      (node (ref "Q2") (pin "5") (pinfunction "G_5") (pintype "passive"))
      (node (ref "R21") (pin "1") (pinfunction "1_1") (pintype "passive"))
      (node (ref "R22") (pin "2") (pinfunction "2_2") (pintype "passive"))
    )
    (net (code "55") (name "Net-(U1-3V3OUT)") (class "Default")
      (node (ref "C2") (pin "1") (pinfunction "1_1") (pintype "passive"))
      (node (ref "U1") (pin "3") (pinfunction "3V3OUT_3") (pintype "output"))
    )
    (net (code "56") (name "Net-(U1-CBUS0)") (class "Default")
      (node (ref "R5") (pin "2") (pinfunction "2_2") (pintype "passive"))
      (node (ref "U1") (pin "6") (pinfunction "CBUS0_6") (pintype "bidirectional"))
    )
    (net (code "57") (name "Net-(U1-RTS#)") (class "Default")
      (node (ref "C5") (pin "1") (pinfunction "1_1") (pintype "passive"))
      (node (ref "U1") (pin "8") (pinfunction "RTS#_8") (pintype "output"))
    )
    (net (code "58") (name "Net-(U1-RXD)") (class "Default")
      (node (ref "R27") (pin "1") (pinfunction "1_1") (pintype "passive"))
      (node (ref "U1") (pin "10") (pinfunction "RXD_10") (pintype "input"))
    )
    (net (code "59") (name "Net-(U1-TXD)") (class "Default")
      (node (ref "R28") (pin "1") (pinfunction "1_1") (pintype "passive"))
      (node (ref "U1") (pin "7") (pinfunction "TXD_7") (pintype "output"))
    )
    (net (code "60") (name "Net-(U1-USBDM)") (class "Default")
      (node (ref "R1") (pin "2") (pinfunction "2_2") (pintype "passive"))
      (node (ref "U1") (pin "1") (pinfunction "USBDM_1") (pintype "bidirectional"))
    )
    (net (code "61") (name "Net-(U1-USBDP)") (class "Default")
      (node (ref "R2") (pin "2") (pinfunction "2_2") (pintype "passive"))
      (node (ref "U1") (pin "12") (pinfunction "USBDP_12") (pintype "bidirectional"))
    )
    (net (code "62") (name "Net-(U1-~{RESET#})") (class "Default")
      (node (ref "R3") (pin "1") (pinfunction "1_1") (pintype "passive"))
      (node (ref "U1") (pin "2") (pinfunction "~{RESET#}_2") (pintype "input"))
    )
    (net (code "63") (name "Net-(U3-PROG)") (class "Default")
      (node (ref "R24") (pin "1") (pinfunction "1_1") (pintype "passive"))
      (node (ref "U3") (pin "2") (pinfunction "PROG_2") (pintype "bidirectional"))
    )
    (net (code "64") (name "Net-(U3-~{CHRG})") (class "Default")
      (node (ref "R12") (pin "2") (pinfunction "2_2") (pintype "passive"))
      (node (ref "U3") (pin "7") (pinfunction "~{CHRG}_7") (pintype "bidirectional"))
    )
    (net (code "65") (name "Net-(U3-~{STDBY})") (class "Default")
      (node (ref "R11") (pin "2") (pinfunction "2_2") (pintype "passive"))
      (node (ref "U3") (pin "6") (pinfunction "~{STDBY}_6") (pintype "bidirectional"))
    )
    (net (code "66") (name "unconnected-(IC2-CLKO-Pad2)") (class "Default")
      (node (ref "IC2") (pin "2") (pinfunction "CLKO_2") (pintype "bidirectional"))
    )
    (net (code "67") (name "unconnected-(IC2-CLKOE-Pad4)") (class "Default")
      (node (ref "IC2") (pin "4") (pinfunction "CLKOE_4") (pintype "bidirectional"))
    )
    (net (code "68") (name "unconnected-(IC2-EVI-Pad7)") (class "Default")
      (node (ref "IC2") (pin "7") (pinfunction "EVI_7") (pintype "bidirectional"))
    )
    (net (code "69") (name "unconnected-(IC5-NC-Pad5)") (class "Default")
      (node (ref "IC5") (pin "5") (pinfunction "NC_5") (pintype "bidirectional"))
    )
    (net (code "70") (name "unconnected-(J2-SBU1-PadA8)") (class "Default")
      (node (ref "J2") (pin "A8") (pinfunction "SBU1_A8") (pintype "bidirectional"))
    )
    (net (code "71") (name "unconnected-(J2-SBU2-PadB8)") (class "Default")
      (node (ref "J2") (pin "B8") (pinfunction "SBU2_B8") (pintype "bidirectional"))
    )
    (net (code "72") (name "unconnected-(LCD1-PadM1)") (class "Default")
      (node (ref "LCD1") (pin "M1") (pinfunction "M1_M1") (pintype "bidirectional"))
    )
    (net (code "73") (name "unconnected-(LCD1-PadM2)") (class "Default")
      (node (ref "LCD1") (pin "M2") (pinfunction "M2_M2") (pintype "bidirectional"))
    )
    (net (code "74") (name "unconnected-(LCD1-REC-Pad11)") (class "Default")
      (node (ref "LCD1") (pin "11") (pinfunction "REC_11") (pintype "bidirectional"))
    )
    (net (code "75") (name "unconnected-(LCD1-RECO{slash}NC-Pad5)") (class "Default")
      (node (ref "LCD1") (pin "5") (pinfunction "RECO/NC_5") (pintype "bidirectional"))
    )
    (net (code "76") (name "unconnected-(LCD1-VHTEST_NC-Pad9)") (class "Default")
      (node (ref "LCD1") (pin "9") (pinfunction "VHTEST_NC_9") (pintype "bidirectional"))
    )
    (net (code "77") (name "unconnected-(LCD1-VHTEST_REF-Pad10)") (class "Default")
      (node (ref "LCD1") (pin "10") (pinfunction "VHTEST_REF_10") (pintype "bidirectional"))
    )
    (net (code "78") (name "unconnected-(SPI-NA1-Pad7)") (class "Default")
      (node (ref "SPI") (pin "7") (pinfunction "NA1_7") (pintype "bidirectional"))
    )
    (net (code "79") (name "unconnected-(SPI-NTRST-Pad8)") (class "Default")
      (node (ref "SPI") (pin "8") (pinfunction "NTRST_8") (pintype "bidirectional"))
    )
    (net (code "80") (name "unconnected-(U1-CTS#-Pad11)") (class "Default")
      (node (ref "U1") (pin "11") (pinfunction "CTS#_11") (pintype "input"))
    )
  )
)
